# SyamPaladugu_HackerCard__HackerCardSchem.net
KiCad netlist of a schematic drawn in Altium Designer
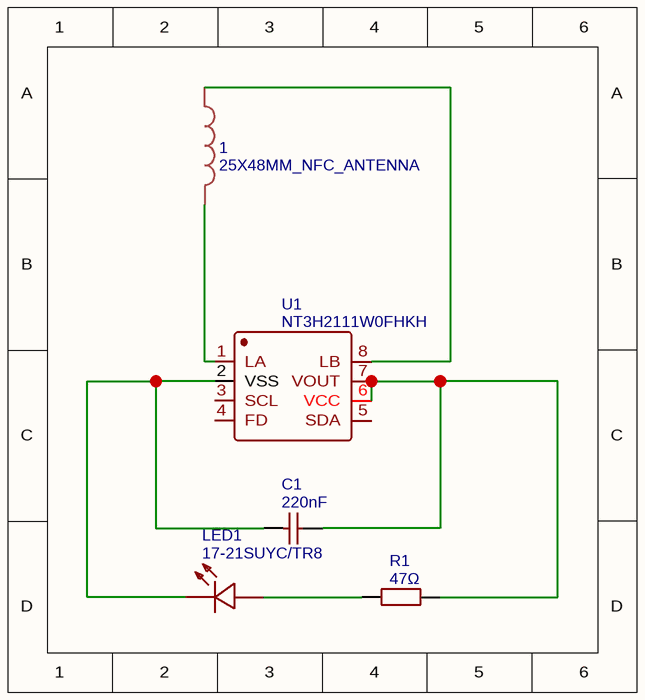
[diagram p0: SyamPaladugu_HackerCard__HackerCardSchematic.schdoc]

(export (version "E")
  (design (tool "Eeschema 10.0.6"))
  (components
    (comp (ref "1")
      (value "25X48MM_NFC_ANTENNA")
      (fields (field (name "CONTRIBUTOR") "smirzaunsu"))
      (libsource (lib "altium-import") (part "root_0_25X48MM_NFC_ANTENNA_"))
    )
    (comp (ref "C1")
      (value "220nF")
      (fields
        (field (name "MANUFACTURER PART") "CL10B224KB8NNNC")
        (field (name "MANUFACTURER") "SAMSUNG(三星)")
      )
      (libsource (lib "altium-import") (part "root_0_220nF_"))
    )
    (comp (ref "LED1")
      (value "17-21SUYC/TR8")
      (fields (field (name "MANUFACTURER") "KENTO") (field (name "MANUFACTURER PART") "KT-0805黄灯"))
      (libsource (lib "altium-import") (part "root_0_17-21SUYC/TR8_"))
    )
    (comp (ref "R1")
      (value "47Ω")
      (fields
        (field (name "MANUFACTURER") "UNI-ROYAL(厚声)")
        (field (name "MANUFACTURER PART") "0603WAF470JT5E")
      )
      (libsource (lib "altium-import") (part "root_0_47Ω_"))
    )
    (comp (ref "U1")
      (value "NT3H2111W0FHKH")
      (fields (field (name "MANUFACTURER") "NXP(恩智浦)") (field (name "CONTRIBUTOR") "LCSC"))
      (libsource (lib "altium-import") (part "root_0_NT3H2111W0FHKH_"))
    )
  )
  (nets
    (net (code "1") (name "Net-(LED1-+)") (class "Default")
      (node (ref "LED1") (pin "1") (pinfunction "+_1") (pintype "passive"))
      (node (ref "R1") (pin "1") (pinfunction "1_1") (pintype "passive"))
    )
    (net (code "2") (name "Net-(LED1--)") (class "Default")
      (node (ref "C1") (pin "1") (pinfunction "1_1") (pintype "passive"))
      (node (ref "LED1") (pin "2") (pinfunction "-_2") (pintype "passive"))
      (node (ref "U1") (pin "2") (pinfunction "VSS_2") (pintype "passive"))
    )
    (net (code "3") (name "Net-(U1-LA)") (class "Default")
      (node (ref "1") (pin "P$2") (pinfunction "P$2_P$2") (pintype "passive"))
      (node (ref "U1") (pin "1") (pinfunction "LA_1") (pintype "passive"))
    )
    (net (code "4") (name "Net-(U1-LB)") (class "Default")
      (node (ref "1") (pin "P$1") (pinfunction "P$1_P$1") (pintype "passive"))
      (node (ref "U1") (pin "8") (pinfunction "LB_8") (pintype "passive"))
    )
    (net (code "5") (name "Net-(U1-VCC)") (class "Default")
      (node (ref "C1") (pin "2") (pinfunction "2_2") (pintype "passive"))
      (node (ref "R1") (pin "2") (pinfunction "2_2") (pintype "passive"))
      (node (ref "U1") (pin "6") (pinfunction "VCC_6") (pintype "passive"))
      (node (ref "U1") (pin "7") (pinfunction "VOUT_7") (pintype "passive"))
    )
    (net (code "6") (name "unconnected-(U1-FD-Pad4)") (class "Default")
      (node (ref "U1") (pin "4") (pinfunction "FD_4") (pintype "passive"))
    )
    (net (code "7") (name "unconnected-(U1-SCL-Pad3)") (class "Default")
      (node (ref "U1") (pin "3") (pinfunction "SCL_3") (pintype "passive"))
    )
    (net (code "8") (name "unconnected-(U1-SDA-Pad5)") (class "Default")
      (node (ref "U1") (pin "5") (pinfunction "SDA_5") (pintype "passive"))
    )
  )
)
